# MCU_8ch_DRL.net
KiCad netlist of a schematic drawn in Altium Designer
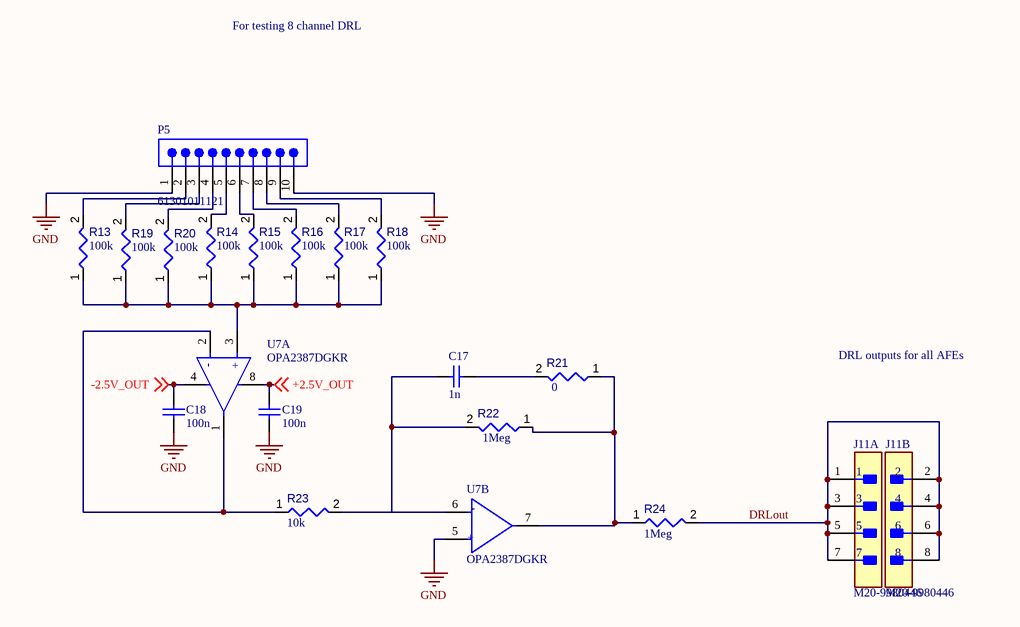
[diagram p0: MCU_8ch_DRL.SchDoc]

(export (version "E")
  (design (tool "Eeschema 10.0.6"))
  (components
    (comp (ref "C17")
      (value "1n")
      (footprint "WCAP-CSGP_0402_L1W0.5H0.5")
      (description "CAP CER 10000PF 50V X7R 0402")
      (fields (field (name "TOLERANCE") "10%"))
      (libsource (lib "Altium Content Vault") (part "Capacitor_Non-Polarized"))
    )
    (comp (ref "C18")
      (value "100n")
      (footprint "WCAP-CSGP_0402_L1W0.5H0.5")
      (description "CAP CER 10000PF 50V X7R 0402")
      (fields (field (name "TOLERANCE") "10%"))
      (libsource (lib "Altium Content Vault") (part "Capacitor_Non-Polarized"))
    )
    (comp (ref "C19")
      (value "100n")
      (footprint "WCAP-CSGP_0402_L1W0.5H0.5")
      (description "CAP CER 10000PF 50V X7R 0402")
      (fields (field (name "TOLERANCE") "10%"))
      (libsource (lib "Altium Content Vault") (part "Capacitor_Non-Polarized"))
    )
    (comp (ref "J11")
      (value "M20-9980446")
      (footprint "FP-M20-9980446-MFG")
      (description "CONN HEADER VERT 8POS 2.54MM")
      (libsource (lib "") (part "811e954b9c034aa737de4d9295cbe7e_1"))
    )
    (comp (ref "P5")
      (value "61301011121")
      (footprint "61301011121")
      (libsource (lib "Altium Content Vault") (part "Header_Male_1R_10P"))
    )
    (comp (ref "R13")
      (value "100k")
      (footprint "RESC1005X40X25ML05T05")
      (description "Chip Resistor, 4.7 KOhm, +/- 1%, 63 mW, -55 to 155 degC, 0402 (1005 Metric)")
      (fields (field (name "TOLERANCE") "1%") (field (name "POWER") "63mW"))
      (libsource (lib "Christian Fenger") (part "RES-2"))
    )
    (comp (ref "R14")
      (value "100k")
      (footprint "RESC1005X40X25ML05T05")
      (description "Chip Resistor, 4.7 KOhm, +/- 1%, 63 mW, -55 to 155 degC, 0402 (1005 Metric)")
      (fields (field (name "TOLERANCE") "1%") (field (name "POWER") "63mW"))
      (libsource (lib "Christian Fenger") (part "RES-2"))
    )
    (comp (ref "R15")
      (value "100k")
      (footprint "RESC1005X40X25ML05T05")
      (description "Chip Resistor, 4.7 KOhm, +/- 1%, 63 mW, -55 to 155 degC, 0402 (1005 Metric)")
      (fields (field (name "TOLERANCE") "1%") (field (name "POWER") "63mW"))
      (libsource (lib "Christian Fenger") (part "RES-2"))
    )
    (comp (ref "R16")
      (value "100k")
      (footprint "RESC1005X40X25ML05T05")
      (description "Chip Resistor, 4.7 KOhm, +/- 1%, 63 mW, -55 to 155 degC, 0402 (1005 Metric)")
      (fields (field (name "TOLERANCE") "1%") (field (name "POWER") "63mW"))
      (libsource (lib "Christian Fenger") (part "RES-2"))
    )
    (comp (ref "R17")
      (value "100k")
      (footprint "RESC1005X40X25ML05T05")
      (description "Chip Resistor, 4.7 KOhm, +/- 1%, 63 mW, -55 to 155 degC, 0402 (1005 Metric)")
      (fields (field (name "TOLERANCE") "1%") (field (name "POWER") "63mW"))
      (libsource (lib "Christian Fenger") (part "RES-2"))
    )
    (comp (ref "R18")
      (value "100k")
      (footprint "RESC1005X40X25ML05T05")
      (description "Chip Resistor, 4.7 KOhm, +/- 1%, 63 mW, -55 to 155 degC, 0402 (1005 Metric)")
      (fields (field (name "TOLERANCE") "1%") (field (name "POWER") "63mW"))
      (libsource (lib "Christian Fenger") (part "RES-2"))
    )
    (comp (ref "R19")
      (value "100k")
      (footprint "RESC1005X40X25ML05T05")
      (description "Chip Resistor, 4.7 KOhm, +/- 1%, 63 mW, -55 to 155 degC, 0402 (1005 Metric)")
      (fields (field (name "TOLERANCE") "1%") (field (name "POWER") "63mW"))
      (libsource (lib "Christian Fenger") (part "RES-2"))
    )
    (comp (ref "R20")
      (value "100k")
      (footprint "RESC1005X40X25ML05T05")
      (description "Chip Resistor, 4.7 KOhm, +/- 1%, 63 mW, -55 to 155 degC, 0402 (1005 Metric)")
      (fields (field (name "TOLERANCE") "1%") (field (name "POWER") "63mW"))
      (libsource (lib "Christian Fenger") (part "RES-2"))
    )
    (comp (ref "R21")
      (value "0")
      (footprint "RESC1005X40X25ML05T05")
      (description "Chip Resistor, 4.7 KOhm, +/- 1%, 63 mW, -55 to 155 degC, 0402 (1005 Metric)")
      (fields (field (name "TOLERANCE") "1%") (field (name "POWER") "63mW"))
      (libsource (lib "Christian Fenger") (part "RES-2"))
    )
    (comp (ref "R22")
      (value "1Meg")
      (footprint "RESC1005X40X25ML05T05")
      (description "Chip Resistor, 4.7 KOhm, +/- 1%, 63 mW, -55 to 155 degC, 0402 (1005 Metric)")
      (fields (field (name "TOLERANCE") "1%") (field (name "POWER") "63mW"))
      (libsource (lib "Christian Fenger") (part "RES-2"))
    )
    (comp (ref "R23")
      (value "10k")
      (footprint "RESC1005X40X25ML05T05")
      (description "Chip Resistor, 4.7 KOhm, +/- 1%, 63 mW, -55 to 155 degC, 0402 (1005 Metric)")
      (fields (field (name "TOLERANCE") "1%") (field (name "POWER") "63mW"))
      (libsource (lib "Christian Fenger") (part "RES-2"))
    )
    (comp (ref "R24")
      (value "1Meg")
      (footprint "RESC1005X40X25ML05T05")
      (description "Chip Resistor, 4.7 KOhm, +/- 1%, 63 mW, -55 to 155 degC, 0402 (1005 Metric)")
      (fields (field (name "TOLERANCE") "1%") (field (name "POWER") "63mW"))
      (libsource (lib "Christian Fenger") (part "RES-2"))
    )
    (comp (ref "U7")
      (value "OPA2387DGKR")
      (footprint "FP-DGK0008A-IPC_B")
      (description "ULTRA-HIGH PRECISION, ZERO-DRIFT")
      (libsource (lib "Altium Content Vault") (part "499df5fc91ff7ad023bcaf249d8becd"))
    )
  )
  (nets
    (net (code "1") (name "+2.5V_OUT") (class "Default")
      (node (ref "C19") (pin "2") (pinfunction "2_2") (pintype "passive"))
      (node (ref "U7") (pin "8") (pinfunction "V+_8") (pintype "power_in"))
    )
    (net (code "2") (name "-2.5V_OUT") (class "Default")
      (node (ref "C18") (pin "2") (pinfunction "2_2") (pintype "passive"))
      (node (ref "U7") (pin "4") (pinfunction "V-_4") (pintype "power_in"))
    )
    (net (code "3") (name "/DRLout") (class "Default")
      (node (ref "J11") (pin "1") (pinfunction "1_1") (pintype "passive"))
      (node (ref "J11") (pin "2") (pinfunction "2_2") (pintype "passive"))
      (node (ref "J11") (pin "3") (pinfunction "3_3") (pintype "passive"))
      (node (ref "J11") (pin "4") (pinfunction "4_4") (pintype "passive"))
      (node (ref "J11") (pin "5") (pinfunction "5_5") (pintype "passive"))
      (node (ref "J11") (pin "6") (pinfunction "6_6") (pintype "passive"))
      (node (ref "J11") (pin "7") (pinfunction "7_7") (pintype "passive"))
      (node (ref "J11") (pin "8") (pinfunction "8_8") (pintype "passive"))
      (node (ref "R24") (pin "2") (pinfunction "2_2") (pintype "passive"))
    )
    (net (code "4") (name "GND") (class "Default")
      (node (ref "C18") (pin "1") (pinfunction "1_1") (pintype "passive"))
      (node (ref "C19") (pin "1") (pinfunction "1_1") (pintype "passive"))
      (node (ref "P5") (pin "1") (pinfunction "1_1") (pintype "passive"))
      (node (ref "P5") (pin "10") (pinfunction "10_10") (pintype "passive"))
      (node (ref "U7") (pin "5") (pinfunction "+IN_B_5") (pintype "tri_state"))
    )
    (net (code "5") (name "Net-(C17-Pad1)") (class "Default")
      (node (ref "C17") (pin "1") (pinfunction "1_1") (pintype "passive"))
      (node (ref "R21") (pin "2") (pinfunction "2_2") (pintype "passive"))
    )
    (net (code "6") (name "Net-(P5-Pad2)") (class "Default")
      (node (ref "P5") (pin "2") (pinfunction "2_2") (pintype "passive"))
      (node (ref "R13") (pin "2") (pinfunction "2_2") (pintype "passive"))
    )
    (net (code "7") (name "Net-(P5-Pad3)") (class "Default")
      (node (ref "P5") (pin "3") (pinfunction "3_3") (pintype "passive"))
      (node (ref "R19") (pin "2") (pinfunction "2_2") (pintype "passive"))
    )
    (net (code "8") (name "Net-(P5-Pad4)") (class "Default")
      (node (ref "P5") (pin "4") (pinfunction "4_4") (pintype "passive"))
      (node (ref "R20") (pin "2") (pinfunction "2_2") (pintype "passive"))
    )
    (net (code "9") (name "Net-(P5-Pad5)") (class "Default")
      (node (ref "P5") (pin "5") (pinfunction "5_5") (pintype "passive"))
      (node (ref "R14") (pin "2") (pinfunction "2_2") (pintype "passive"))
    )
    (net (code "10") (name "Net-(P5-Pad6)") (class "Default")
      (node (ref "P5") (pin "6") (pinfunction "6_6") (pintype "passive"))
      (node (ref "R15") (pin "2") (pinfunction "2_2") (pintype "passive"))
    )
    (net (code "11") (name "Net-(P5-Pad7)") (class "Default")
      (node (ref "P5") (pin "7") (pinfunction "7_7") (pintype "passive"))
      (node (ref "R16") (pin "2") (pinfunction "2_2") (pintype "passive"))
    )
    (net (code "12") (name "Net-(P5-Pad8)") (class "Default")
      (node (ref "P5") (pin "8") (pinfunction "8_8") (pintype "passive"))
      (node (ref "R17") (pin "2") (pinfunction "2_2") (pintype "passive"))
    )
    (net (code "13") (name "Net-(P5-Pad9)") (class "Default")
      (node (ref "P5") (pin "9") (pinfunction "9_9") (pintype "passive"))
      (node (ref "R18") (pin "2") (pinfunction "2_2") (pintype "passive"))
    )
    (net (code "14") (name "Net-(U7A-+IN_A)") (class "Default")
      (node (ref "R13") (pin "1") (pinfunction "1_1") (pintype "passive"))
      (node (ref "R14") (pin "1") (pinfunction "1_1") (pintype "passive"))
      (node (ref "R15") (pin "1") (pinfunction "1_1") (pintype "passive"))
      (node (ref "R16") (pin "1") (pinfunction "1_1") (pintype "passive"))
      (node (ref "R17") (pin "1") (pinfunction "1_1") (pintype "passive"))
      (node (ref "R18") (pin "1") (pinfunction "1_1") (pintype "passive"))
      (node (ref "R19") (pin "1") (pinfunction "1_1") (pintype "passive"))
      (node (ref "R20") (pin "1") (pinfunction "1_1") (pintype "passive"))
      (node (ref "U7") (pin "3") (pinfunction "+IN_A_3") (pintype "tri_state"))
    )
    (net (code "15") (name "Net-(U7A--IN_A)") (class "Default")
      (node (ref "R23") (pin "1") (pinfunction "1_1") (pintype "passive"))
      (node (ref "U7") (pin "1") (pinfunction "OUT_A_1") (pintype "passive"))
      (node (ref "U7") (pin "2") (pinfunction "-IN_A_2") (pintype "tri_state"))
    )
    (net (code "16") (name "Net-(U7B--IN_B)") (class "Default")
      (node (ref "C17") (pin "2") (pinfunction "2_2") (pintype "passive"))
      (node (ref "R22") (pin "2") (pinfunction "2_2") (pintype "passive"))
      (node (ref "R23") (pin "2") (pinfunction "2_2") (pintype "passive"))
      (node (ref "U7") (pin "6") (pinfunction "-IN_B_6") (pintype "tri_state"))
    )
    (net (code "17") (name "Net-(U7B-OUT_B)") (class "Default")
      (node (ref "R21") (pin "1") (pinfunction "1_1") (pintype "passive"))
      (node (ref "R22") (pin "1") (pinfunction "1_1") (pintype "passive"))
      (node (ref "R24") (pin "1") (pinfunction "1_1") (pintype "passive"))
      (node (ref "U7") (pin "7") (pinfunction "OUT_B_7") (pintype "passive"))
    )
  )
)
